# SCH_09_InOut_Terminal.net
KiCad netlist of a schematic drawn in Altium Designer
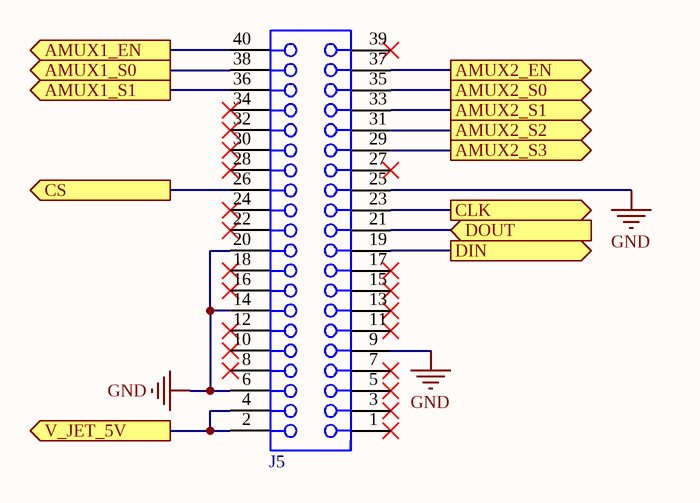
[diagram p0: SCH_09_InOut_Terminal.SchDoc]

(export (version "E")
  (design (tool "Eeschema 10.0.6"))
  (components
    (comp (ref "J5")
      (value "613040243121")
      (footprint "613040243121")
      (description "WR-PHD Socket Header, THT, Angled, pitch 2.54mm, 2 Row, 40P")
      (fields (field (name "MANUFACTURER") "Wurth Elektronik"))
      (libsource (lib "Altium_WR-PHD (rev24a)") (part "613040243121"))
    )
  )
  (nets
    (net (code "1") (name "/AMUX1_EN") (class "Default")
      (node (ref "J5") (pin "40") (pinfunction "40_40") (pintype "passive"))
    )
    (net (code "2") (name "/AMUX1_S0") (class "Default")
      (node (ref "J5") (pin "38") (pinfunction "38_38") (pintype "passive"))
    )
    (net (code "3") (name "/AMUX1_S1") (class "Default")
      (node (ref "J5") (pin "36") (pinfunction "36_36") (pintype "passive"))
    )
    (net (code "4") (name "/AMUX2_EN") (class "Default")
      (node (ref "J5") (pin "37") (pinfunction "37_37") (pintype "passive"))
    )
    (net (code "5") (name "/AMUX2_S0") (class "Default")
      (node (ref "J5") (pin "35") (pinfunction "35_35") (pintype "passive"))
    )
    (net (code "6") (name "/AMUX2_S1") (class "Default")
      (node (ref "J5") (pin "33") (pinfunction "33_33") (pintype "passive"))
    )
    (net (code "7") (name "/AMUX2_S2") (class "Default")
      (node (ref "J5") (pin "31") (pinfunction "31_31") (pintype "passive"))
    )
    (net (code "8") (name "/AMUX2_S3") (class "Default")
      (node (ref "J5") (pin "29") (pinfunction "29_29") (pintype "passive"))
    )
    (net (code "9") (name "/CLK") (class "Default")
      (node (ref "J5") (pin "23") (pinfunction "23_23") (pintype "passive"))
    )
    (net (code "10") (name "/CS") (class "Default")
      (node (ref "J5") (pin "26") (pinfunction "26_26") (pintype "passive"))
    )
    (net (code "11") (name "/DIN") (class "Default")
      (node (ref "J5") (pin "19") (pinfunction "19_19") (pintype "passive"))
    )
    (net (code "12") (name "/DOUT") (class "Default")
      (node (ref "J5") (pin "21") (pinfunction "21_21") (pintype "passive"))
    )
    (net (code "13") (name "/V_JET_5V") (class "Default")
      (node (ref "J5") (pin "2") (pinfunction "2_2") (pintype "passive"))
      (node (ref "J5") (pin "4") (pinfunction "4_4") (pintype "passive"))
    )
    (net (code "14") (name "GND") (class "Default")
      (node (ref "J5") (pin "14") (pinfunction "14_14") (pintype "passive"))
      (node (ref "J5") (pin "20") (pinfunction "20_20") (pintype "passive"))
      (node (ref "J5") (pin "25") (pinfunction "25_25") (pintype "passive"))
      (node (ref "J5") (pin "6") (pinfunction "6_6") (pintype "passive"))
      (node (ref "J5") (pin "9") (pinfunction "9_9") (pintype "passive"))
    )
    (net (code "15") (name "unconnected-(J5-Pad1)") (class "Default")
      (node (ref "J5") (pin "1") (pinfunction "1_1") (pintype "passive+no_connect"))
    )
    (net (code "16") (name "unconnected-(J5-Pad3)") (class "Default")
      (node (ref "J5") (pin "3") (pinfunction "3_3") (pintype "passive+no_connect"))
    )
    (net (code "17") (name "unconnected-(J5-Pad5)") (class "Default")
      (node (ref "J5") (pin "5") (pinfunction "5_5") (pintype "passive+no_connect"))
    )
    (net (code "18") (name "unconnected-(J5-Pad7)") (class "Default")
      (node (ref "J5") (pin "7") (pinfunction "7_7") (pintype "passive+no_connect"))
    )
    (net (code "19") (name "unconnected-(J5-Pad8)") (class "Default")
      (node (ref "J5") (pin "8") (pinfunction "8_8") (pintype "passive+no_connect"))
    )
    (net (code "20") (name "unconnected-(J5-Pad10)") (class "Default")
      (node (ref "J5") (pin "10") (pinfunction "10_10") (pintype "passive+no_connect"))
    )
    (net (code "21") (name "unconnected-(J5-Pad11)") (class "Default")
      (node (ref "J5") (pin "11") (pinfunction "11_11") (pintype "passive+no_connect"))
    )
    (net (code "22") (name "unconnected-(J5-Pad12)") (class "Default")
      (node (ref "J5") (pin "12") (pinfunction "12_12") (pintype "passive+no_connect"))
    )
    (net (code "23") (name "unconnected-(J5-Pad13)") (class "Default")
      (node (ref "J5") (pin "13") (pinfunction "13_13") (pintype "passive+no_connect"))
    )
    (net (code "24") (name "unconnected-(J5-Pad15)") (class "Default")
      (node (ref "J5") (pin "15") (pinfunction "15_15") (pintype "passive+no_connect"))
    )
    (net (code "25") (name "unconnected-(J5-Pad16)") (class "Default")
      (node (ref "J5") (pin "16") (pinfunction "16_16") (pintype "passive+no_connect"))
    )
    (net (code "26") (name "unconnected-(J5-Pad17)") (class "Default")
      (node (ref "J5") (pin "17") (pinfunction "17_17") (pintype "passive+no_connect"))
    )
    (net (code "27") (name "unconnected-(J5-Pad18)") (class "Default")
      (node (ref "J5") (pin "18") (pinfunction "18_18") (pintype "passive+no_connect"))
    )
    (net (code "28") (name "unconnected-(J5-Pad22)") (class "Default")
      (node (ref "J5") (pin "22") (pinfunction "22_22") (pintype "passive+no_connect"))
    )
    (net (code "29") (name "unconnected-(J5-Pad24)") (class "Default")
      (node (ref "J5") (pin "24") (pinfunction "24_24") (pintype "passive+no_connect"))
    )
    (net (code "30") (name "unconnected-(J5-Pad27)") (class "Default")
      (node (ref "J5") (pin "27") (pinfunction "27_27") (pintype "passive+no_connect"))
    )
    (net (code "31") (name "unconnected-(J5-Pad28)") (class "Default")
      (node (ref "J5") (pin "28") (pinfunction "28_28") (pintype "passive+no_connect"))
    )
    (net (code "32") (name "unconnected-(J5-Pad30)") (class "Default")
      (node (ref "J5") (pin "30") (pinfunction "30_30") (pintype "passive+no_connect"))
    )
    (net (code "33") (name "unconnected-(J5-Pad32)") (class "Default")
      (node (ref "J5") (pin "32") (pinfunction "32_32") (pintype "passive+no_connect"))
    )
    (net (code "34") (name "unconnected-(J5-Pad34)") (class "Default")
      (node (ref "J5") (pin "34") (pinfunction "34_34") (pintype "passive+no_connect"))
    )
    (net (code "35") (name "unconnected-(J5-Pad39)") (class "Default")
      (node (ref "J5") (pin "39") (pinfunction "39_39") (pintype "passive+no_connect"))
    )
  )
)
